# can-weichendecoder-magnet_0_2.net
KiCad netlist of a schematic drawn in EAGLE
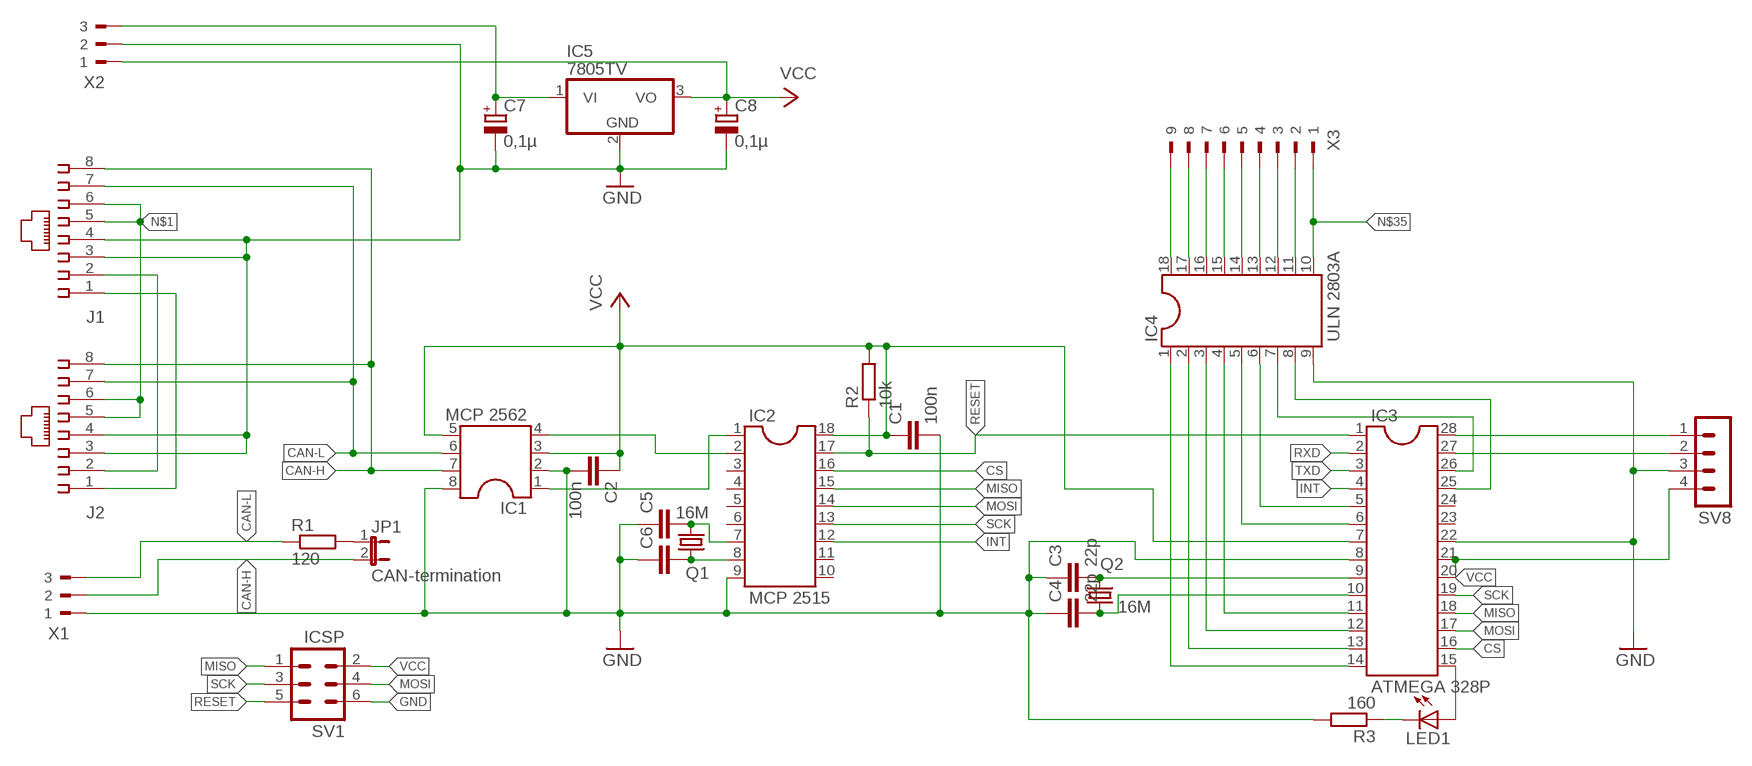
[diagram p0: schematic, sheet 1]

(export (version "E")
  (design (tool "Eeschema 10.0.6"))
  (components
    (comp (ref "C1")
      (value "100n")
      (footprint "eagle-import:C0805")
      (libsource (lib "eagle-import") (part "C-EUC0805"))
    )
    (comp (ref "C2")
      (value "100n")
      (footprint "eagle-import:C0805")
      (libsource (lib "eagle-import") (part "C-EUC0805"))
    )
    (comp (ref "C3")
      (value "22p")
      (footprint "eagle-import:C0805")
      (libsource (lib "eagle-import") (part "C-EUC0805"))
    )
    (comp (ref "C4")
      (value "22p")
      (footprint "eagle-import:C0805")
      (libsource (lib "eagle-import") (part "C-EUC0805"))
    )
    (comp (ref "C5")
      (value "C-EUC0805")
      (footprint "eagle-import:C0805")
      (libsource (lib "eagle-import") (part "C-EUC0805"))
    )
    (comp (ref "C6")
      (value "C-EUC0805")
      (footprint "eagle-import:C0805")
      (libsource (lib "eagle-import") (part "C-EUC0805"))
    )
    (comp (ref "C7")
      (value "0,1µ")
      (footprint "eagle-import:E2,5-6")
      (libsource (lib "eagle-import") (part "CPOL-EUE2.5-6"))
    )
    (comp (ref "C8")
      (value "0,1µ")
      (footprint "eagle-import:E2,5-6")
      (libsource (lib "eagle-import") (part "CPOL-EUE2.5-6"))
    )
    (comp (ref "IC1")
      (value "MCP 2562")
      (footprint "eagle-import:SOCKET-08")
      (libsource (lib "eagle-import") (part "DIL8S"))
    )
    (comp (ref "IC2")
      (value "MCP 2515")
      (footprint "eagle-import:SOCKET-18")
      (libsource (lib "eagle-import") (part "DIL18S"))
    )
    (comp (ref "IC3")
      (value "ATMEGA 328P")
      (footprint "eagle-import:DIL28-3")
      (libsource (lib "eagle-import") (part "DIL28-3"))
    )
    (comp (ref "IC4")
      (value "ULN 2803A")
      (footprint "eagle-import:SOCKET-18")
      (libsource (lib "eagle-import") (part "DIL18S"))
    )
    (comp (ref "IC5")
      (value "7805TV")
      (footprint "eagle-import:TO220V")
      (libsource (lib "eagle-import") (part "78TV05"))
    )
    (comp (ref "J1")
      (value "215877-7")
      (footprint "eagle-import:215877-7")
      (libsource (lib "eagle-import") (part "215877-7"))
    )
    (comp (ref "J2")
      (value "215877-7")
      (footprint "eagle-import:215877-7")
      (libsource (lib "eagle-import") (part "215877-7"))
    )
    (comp (ref "JP1")
      (value "CAN-termination")
      (footprint "eagle-import:JP1")
      (libsource (lib "eagle-import") (part "JP1E"))
    )
    (comp (ref "LED1")
      (value "LEDCHIP-LED0805")
      (footprint "eagle-import:CHIP-LED0805")
      (libsource (lib "eagle-import") (part "LEDCHIP-LED0805"))
    )
    (comp (ref "Q1")
      (value "16M")
      (footprint "eagle-import:HC49_S")
      (libsource (lib "eagle-import") (part "CRYSTALHC49S"))
    )
    (comp (ref "Q2")
      (value "16M")
      (footprint "eagle-import:HC49_S")
      (libsource (lib "eagle-import") (part "CRYSTALHC49S"))
    )
    (comp (ref "R1")
      (value "120")
      (footprint "eagle-import:R0805")
      (libsource (lib "eagle-import") (part "R-EU_R0805"))
    )
    (comp (ref "R2")
      (value "10k")
      (footprint "eagle-import:R0805")
      (libsource (lib "eagle-import") (part "R-EU_R0805"))
    )
    (comp (ref "R3")
      (value "160")
      (footprint "eagle-import:R0805")
      (libsource (lib "eagle-import") (part "R-EU_R0805"))
    )
    (comp (ref "SV1")
      (value "ICSP")
      (footprint "eagle-import:MA03-2")
      (libsource (lib "eagle-import") (part "MA03-2"))
    )
    (comp (ref "SV8")
      (value "MA04-1")
      (footprint "eagle-import:MA04-1")
      (libsource (lib "eagle-import") (part "MA04-1"))
    )
    (comp (ref "X1")
      (value "90-3")
      (footprint "eagle-import:90-3")
      (libsource (lib "eagle-import") (part "90-3"))
    )
    (comp (ref "X2")
      (value "90-3")
      (footprint "eagle-import:90-3")
      (libsource (lib "eagle-import") (part "90-3"))
    )
    (comp (ref "X3")
      (value "90-9")
      (footprint "eagle-import:90-9")
      (libsource (lib "eagle-import") (part "90-9"))
    )
  )
  (nets
    (net (code "1") (name "CAN-H") (class "Default")
      (node (ref "IC1") (pin "7") (pinfunction "7_7") (pintype "passive"))
      (node (ref "J1") (pin "8") (pinfunction "8_8") (pintype "passive"))
      (node (ref "J2") (pin "8") (pinfunction "8_8") (pintype "passive"))
      (node (ref "JP1") (pin "2") (pinfunction "2_2") (pintype "passive"))
      (node (ref "X1") (pin "2") (pinfunction "2_2") (pintype "passive"))
    )
    (net (code "2") (name "CAN-L") (class "Default")
      (node (ref "IC1") (pin "6") (pinfunction "6_6") (pintype "passive"))
      (node (ref "J1") (pin "7") (pinfunction "7_7") (pintype "passive"))
      (node (ref "J2") (pin "7") (pinfunction "7_7") (pintype "passive"))
      (node (ref "R1") (pin "1") (pinfunction "1_1") (pintype "passive"))
      (node (ref "X1") (pin "3") (pinfunction "3_3") (pintype "passive"))
    )
    (net (code "3") (name "CS") (class "Default")
      (node (ref "IC2") (pin "16") (pinfunction "16_16") (pintype "passive"))
      (node (ref "IC3") (pin "16") (pinfunction "16_16") (pintype "passive"))
    )
    (net (code "4") (name "GND") (class "Default")
      (node (ref "C1") (pin "2") (pinfunction "2_2") (pintype "passive"))
      (node (ref "C2") (pin "2") (pinfunction "2_2") (pintype "passive"))
      (node (ref "C3") (pin "1") (pinfunction "1_1") (pintype "passive"))
      (node (ref "C4") (pin "1") (pinfunction "1_1") (pintype "passive"))
      (node (ref "C5") (pin "1") (pinfunction "1_1") (pintype "passive"))
      (node (ref "C6") (pin "1") (pinfunction "1_1") (pintype "passive"))
      (node (ref "C7") (pin "-") (pinfunction "-_-") (pintype "passive"))
      (node (ref "C8") (pin "-") (pinfunction "-_-") (pintype "passive"))
      (node (ref "IC1") (pin "2") (pinfunction "2_2") (pintype "passive"))
      (node (ref "IC1") (pin "8") (pinfunction "8_8") (pintype "passive"))
      (node (ref "IC2") (pin "9") (pinfunction "9_9") (pintype "passive"))
      (node (ref "IC3") (pin "22") (pinfunction "22_22") (pintype "passive"))
      (node (ref "IC3") (pin "8") (pinfunction "8_8") (pintype "passive"))
      (node (ref "IC4") (pin "9") (pinfunction "9_9") (pintype "passive"))
      (node (ref "IC5") (pin "2") (pinfunction "GND_2") (pintype "passive"))
      (node (ref "J1") (pin "3") (pinfunction "3_3") (pintype "passive"))
      (node (ref "J1") (pin "4") (pinfunction "4_4") (pintype "passive"))
      (node (ref "J2") (pin "3") (pinfunction "3_3") (pintype "passive"))
      (node (ref "J2") (pin "4") (pinfunction "4_4") (pintype "passive"))
      (node (ref "R3") (pin "2") (pinfunction "2_2") (pintype "passive"))
      (node (ref "SV1") (pin "6") (pinfunction "6_6") (pintype "passive"))
      (node (ref "SV8") (pin "3") (pinfunction "3_3") (pintype "passive"))
      (node (ref "X1") (pin "1") (pinfunction "1_1") (pintype "passive"))
      (node (ref "X2") (pin "2") (pinfunction "2_2") (pintype "passive"))
    )
    (net (code "5") (name "INT") (class "Default")
      (node (ref "IC2") (pin "12") (pinfunction "12_12") (pintype "passive"))
      (node (ref "IC3") (pin "4") (pinfunction "4_4") (pintype "passive"))
    )
    (net (code "6") (name "MISO") (class "Default")
      (node (ref "IC2") (pin "15") (pinfunction "15_15") (pintype "passive"))
      (node (ref "IC3") (pin "18") (pinfunction "18_18") (pintype "passive"))
      (node (ref "SV1") (pin "1") (pinfunction "1_1") (pintype "passive"))
    )
    (net (code "7") (name "MOSI") (class "Default")
      (node (ref "IC2") (pin "14") (pinfunction "14_14") (pintype "passive"))
      (node (ref "IC3") (pin "17") (pinfunction "17_17") (pintype "passive"))
      (node (ref "SV1") (pin "4") (pinfunction "4_4") (pintype "passive"))
    )
    (net (code "8") (name "N$1") (class "Default")
      (node (ref "J1") (pin "5") (pinfunction "5_5") (pintype "passive"))
      (node (ref "J1") (pin "6") (pinfunction "6_6") (pintype "passive"))
      (node (ref "J2") (pin "5") (pinfunction "5_5") (pintype "passive"))
      (node (ref "J2") (pin "6") (pinfunction "6_6") (pintype "passive"))
    )
    (net (code "9") (name "N$35") (class "Default")
      (node (ref "IC4") (pin "10") (pinfunction "10_10") (pintype "passive"))
      (node (ref "X3") (pin "1") (pinfunction "1_1") (pintype "passive"))
    )
    (net (code "10") (name "Net-(C3-Pad2)") (class "Default")
      (node (ref "C3") (pin "2") (pinfunction "2_2") (pintype "passive"))
      (node (ref "IC3") (pin "9") (pinfunction "9_9") (pintype "passive"))
      (node (ref "Q2") (pin "2") (pinfunction "2_2") (pintype "passive"))
    )
    (net (code "11") (name "Net-(C4-Pad2)") (class "Default")
      (node (ref "C4") (pin "2") (pinfunction "2_2") (pintype "passive"))
      (node (ref "IC3") (pin "10") (pinfunction "10_10") (pintype "passive"))
      (node (ref "Q2") (pin "1") (pinfunction "1_1") (pintype "passive"))
    )
    (net (code "12") (name "Net-(C5-Pad2)") (class "Default")
      (node (ref "C5") (pin "2") (pinfunction "2_2") (pintype "passive"))
      (node (ref "IC2") (pin "7") (pinfunction "7_7") (pintype "passive"))
      (node (ref "Q1") (pin "2") (pinfunction "2_2") (pintype "passive"))
    )
    (net (code "13") (name "Net-(C6-Pad2)") (class "Default")
      (node (ref "C6") (pin "2") (pinfunction "2_2") (pintype "passive"))
      (node (ref "IC2") (pin "8") (pinfunction "8_8") (pintype "passive"))
      (node (ref "Q1") (pin "1") (pinfunction "1_1") (pintype "passive"))
    )
    (net (code "14") (name "Net-(IC1-Pad1)") (class "Default")
      (node (ref "IC1") (pin "1") (pinfunction "1_1") (pintype "passive"))
      (node (ref "IC2") (pin "1") (pinfunction "1_1") (pintype "passive"))
    )
    (net (code "15") (name "Net-(IC1-Pad4)") (class "Default")
      (node (ref "IC1") (pin "4") (pinfunction "4_4") (pintype "passive"))
      (node (ref "IC2") (pin "2") (pinfunction "2_2") (pintype "passive"))
    )
    (net (code "16") (name "Net-(IC3-Pad5)") (class "Default")
      (node (ref "IC3") (pin "5") (pinfunction "5_5") (pintype "passive"))
      (node (ref "IC4") (pin "6") (pinfunction "6_6") (pintype "passive"))
    )
    (net (code "17") (name "Net-(IC3-Pad6)") (class "Default")
      (node (ref "IC3") (pin "6") (pinfunction "6_6") (pintype "passive"))
      (node (ref "IC4") (pin "5") (pinfunction "5_5") (pintype "passive"))
    )
    (net (code "18") (name "Net-(IC3-Pad11)") (class "Default")
      (node (ref "IC3") (pin "11") (pinfunction "11_11") (pintype "passive"))
      (node (ref "IC4") (pin "4") (pinfunction "4_4") (pintype "passive"))
    )
    (net (code "19") (name "Net-(IC3-Pad12)") (class "Default")
      (node (ref "IC3") (pin "12") (pinfunction "12_12") (pintype "passive"))
      (node (ref "IC4") (pin "3") (pinfunction "3_3") (pintype "passive"))
    )
    (net (code "20") (name "Net-(IC3-Pad13)") (class "Default")
      (node (ref "IC3") (pin "13") (pinfunction "13_13") (pintype "passive"))
      (node (ref "IC4") (pin "2") (pinfunction "2_2") (pintype "passive"))
    )
    (net (code "21") (name "Net-(IC3-Pad14)") (class "Default")
      (node (ref "IC3") (pin "14") (pinfunction "14_14") (pintype "passive"))
      (node (ref "IC4") (pin "1") (pinfunction "1_1") (pintype "passive"))
    )
    (net (code "22") (name "Net-(IC3-Pad15)") (class "Default")
      (node (ref "IC3") (pin "15") (pinfunction "15_15") (pintype "passive"))
      (node (ref "LED1") (pin "A") (pinfunction "A_A") (pintype "passive"))
    )
    (net (code "23") (name "Net-(IC3-Pad25)") (class "Default")
      (node (ref "IC3") (pin "25") (pinfunction "25_25") (pintype "passive"))
      (node (ref "IC4") (pin "8") (pinfunction "8_8") (pintype "passive"))
    )
    (net (code "24") (name "Net-(IC3-Pad26)") (class "Default")
      (node (ref "IC3") (pin "26") (pinfunction "26_26") (pintype "passive"))
      (node (ref "IC4") (pin "7") (pinfunction "7_7") (pintype "passive"))
    )
    (net (code "25") (name "Net-(IC3-Pad27)") (class "Default")
      (node (ref "IC3") (pin "27") (pinfunction "27_27") (pintype "passive"))
      (node (ref "SV8") (pin "2") (pinfunction "2_2") (pintype "passive"))
    )
    (net (code "26") (name "Net-(IC3-Pad28)") (class "Default")
      (node (ref "IC3") (pin "28") (pinfunction "28_28") (pintype "passive"))
      (node (ref "SV8") (pin "1") (pinfunction "1_1") (pintype "passive"))
    )
    (net (code "27") (name "Net-(IC4-Pad11)") (class "Default")
      (node (ref "IC4") (pin "11") (pinfunction "11_11") (pintype "passive"))
      (node (ref "X3") (pin "2") (pinfunction "2_2") (pintype "passive"))
    )
    (net (code "28") (name "Net-(IC4-Pad12)") (class "Default")
      (node (ref "IC4") (pin "12") (pinfunction "12_12") (pintype "passive"))
      (node (ref "X3") (pin "3") (pinfunction "3_3") (pintype "passive"))
    )
    (net (code "29") (name "Net-(IC4-Pad13)") (class "Default")
      (node (ref "IC4") (pin "13") (pinfunction "13_13") (pintype "passive"))
      (node (ref "X3") (pin "4") (pinfunction "4_4") (pintype "passive"))
    )
    (net (code "30") (name "Net-(IC4-Pad14)") (class "Default")
      (node (ref "IC4") (pin "14") (pinfunction "14_14") (pintype "passive"))
      (node (ref "X3") (pin "5") (pinfunction "5_5") (pintype "passive"))
    )
    (net (code "31") (name "Net-(IC4-Pad15)") (class "Default")
      (node (ref "IC4") (pin "15") (pinfunction "15_15") (pintype "passive"))
      (node (ref "X3") (pin "6") (pinfunction "6_6") (pintype "passive"))
    )
    (net (code "32") (name "Net-(IC4-Pad16)") (class "Default")
      (node (ref "IC4") (pin "16") (pinfunction "16_16") (pintype "passive"))
      (node (ref "X3") (pin "7") (pinfunction "7_7") (pintype "passive"))
    )
    (net (code "33") (name "Net-(IC4-Pad17)") (class "Default")
      (node (ref "IC4") (pin "17") (pinfunction "17_17") (pintype "passive"))
      (node (ref "X3") (pin "8") (pinfunction "8_8") (pintype "passive"))
    )
    (net (code "34") (name "Net-(IC4-Pad18)") (class "Default")
      (node (ref "IC4") (pin "18") (pinfunction "18_18") (pintype "passive"))
      (node (ref "X3") (pin "9") (pinfunction "9_9") (pintype "passive"))
    )
    (net (code "35") (name "Net-(IC5-VI)") (class "Default")
      (node (ref "C7") (pin "+") (pinfunction "+_+") (pintype "passive"))
      (node (ref "IC5") (pin "1") (pinfunction "VI_1") (pintype "input"))
      (node (ref "X2") (pin "3") (pinfunction "3_3") (pintype "passive"))
    )
    (net (code "36") (name "Net-(J1-Pad1)") (class "Default")
      (node (ref "J1") (pin "1") (pinfunction "1_1") (pintype "passive"))
      (node (ref "J2") (pin "1") (pinfunction "1_1") (pintype "passive"))
    )
    (net (code "37") (name "Net-(J1-Pad2)") (class "Default")
      (node (ref "J1") (pin "2") (pinfunction "2_2") (pintype "passive"))
      (node (ref "J2") (pin "2") (pinfunction "2_2") (pintype "passive"))
    )
    (net (code "38") (name "Net-(JP1-Pad1)") (class "Default")
      (node (ref "JP1") (pin "1") (pinfunction "1_1") (pintype "passive"))
      (node (ref "R1") (pin "2") (pinfunction "2_2") (pintype "passive"))
    )
    (net (code "39") (name "Net-(LED1-PadC)") (class "Default")
      (node (ref "LED1") (pin "C") (pinfunction "C_C") (pintype "passive"))
      (node (ref "R3") (pin "1") (pinfunction "1_1") (pintype "passive"))
    )
    (net (code "40") (name "RESET") (class "Default")
      (node (ref "IC2") (pin "17") (pinfunction "17_17") (pintype "passive"))
      (node (ref "IC3") (pin "1") (pinfunction "1_1") (pintype "passive"))
      (node (ref "R2") (pin "1") (pinfunction "1_1") (pintype "passive"))
      (node (ref "SV1") (pin "5") (pinfunction "5_5") (pintype "passive"))
    )
    (net (code "41") (name "RXD") (class "Default")
      (node (ref "IC3") (pin "2") (pinfunction "2_2") (pintype "passive"))
    )
    (net (code "42") (name "SCK") (class "Default")
      (node (ref "IC2") (pin "13") (pinfunction "13_13") (pintype "passive"))
      (node (ref "IC3") (pin "19") (pinfunction "19_19") (pintype "passive"))
      (node (ref "SV1") (pin "3") (pinfunction "3_3") (pintype "passive"))
    )
    (net (code "43") (name "TXD") (class "Default")
      (node (ref "IC3") (pin "3") (pinfunction "3_3") (pintype "passive"))
    )
    (net (code "44") (name "VCC") (class "Default")
      (node (ref "C1") (pin "1") (pinfunction "1_1") (pintype "passive"))
      (node (ref "C2") (pin "1") (pinfunction "1_1") (pintype "passive"))
      (node (ref "C8") (pin "+") (pinfunction "+_+") (pintype "passive"))
      (node (ref "IC1") (pin "3") (pinfunction "3_3") (pintype "passive"))
      (node (ref "IC1") (pin "5") (pinfunction "5_5") (pintype "passive"))
      (node (ref "IC2") (pin "18") (pinfunction "18_18") (pintype "passive"))
      (node (ref "IC3") (pin "20") (pinfunction "20_20") (pintype "passive"))
      (node (ref "IC3") (pin "21") (pinfunction "21_21") (pintype "passive"))
      (node (ref "IC3") (pin "7") (pinfunction "7_7") (pintype "passive"))
      (node (ref "IC5") (pin "3") (pinfunction "VO_3") (pintype "passive"))
      (node (ref "R2") (pin "2") (pinfunction "2_2") (pintype "passive"))
      (node (ref "SV1") (pin "2") (pinfunction "2_2") (pintype "passive"))
      (node (ref "SV8") (pin "4") (pinfunction "4_4") (pintype "passive"))
      (node (ref "X2") (pin "1") (pinfunction "1_1") (pintype "passive"))
    )
    (net (code "45") (name "unconnected-(IC2-Pad3)") (class "Default")
      (node (ref "IC2") (pin "3") (pinfunction "3_3") (pintype "passive"))
    )
    (net (code "46") (name "unconnected-(IC2-Pad4)") (class "Default")
      (node (ref "IC2") (pin "4") (pinfunction "4_4") (pintype "passive"))
    )
    (net (code "47") (name "unconnected-(IC2-Pad5)") (class "Default")
      (node (ref "IC2") (pin "5") (pinfunction "5_5") (pintype "passive"))
    )
    (net (code "48") (name "unconnected-(IC2-Pad6)") (class "Default")
      (node (ref "IC2") (pin "6") (pinfunction "6_6") (pintype "passive"))
    )
    (net (code "49") (name "unconnected-(IC2-Pad10)") (class "Default")
      (node (ref "IC2") (pin "10") (pinfunction "10_10") (pintype "passive"))
    )
    (net (code "50") (name "unconnected-(IC2-Pad11)") (class "Default")
      (node (ref "IC2") (pin "11") (pinfunction "11_11") (pintype "passive"))
    )
    (net (code "51") (name "unconnected-(IC3-Pad23)") (class "Default")
      (node (ref "IC3") (pin "23") (pinfunction "23_23") (pintype "passive"))
    )
    (net (code "52") (name "unconnected-(IC3-Pad24)") (class "Default")
      (node (ref "IC3") (pin "24") (pinfunction "24_24") (pintype "passive"))
    )
  )
)
